# bb-7.net
KiCad netlist of a schematic drawn in EAGLE
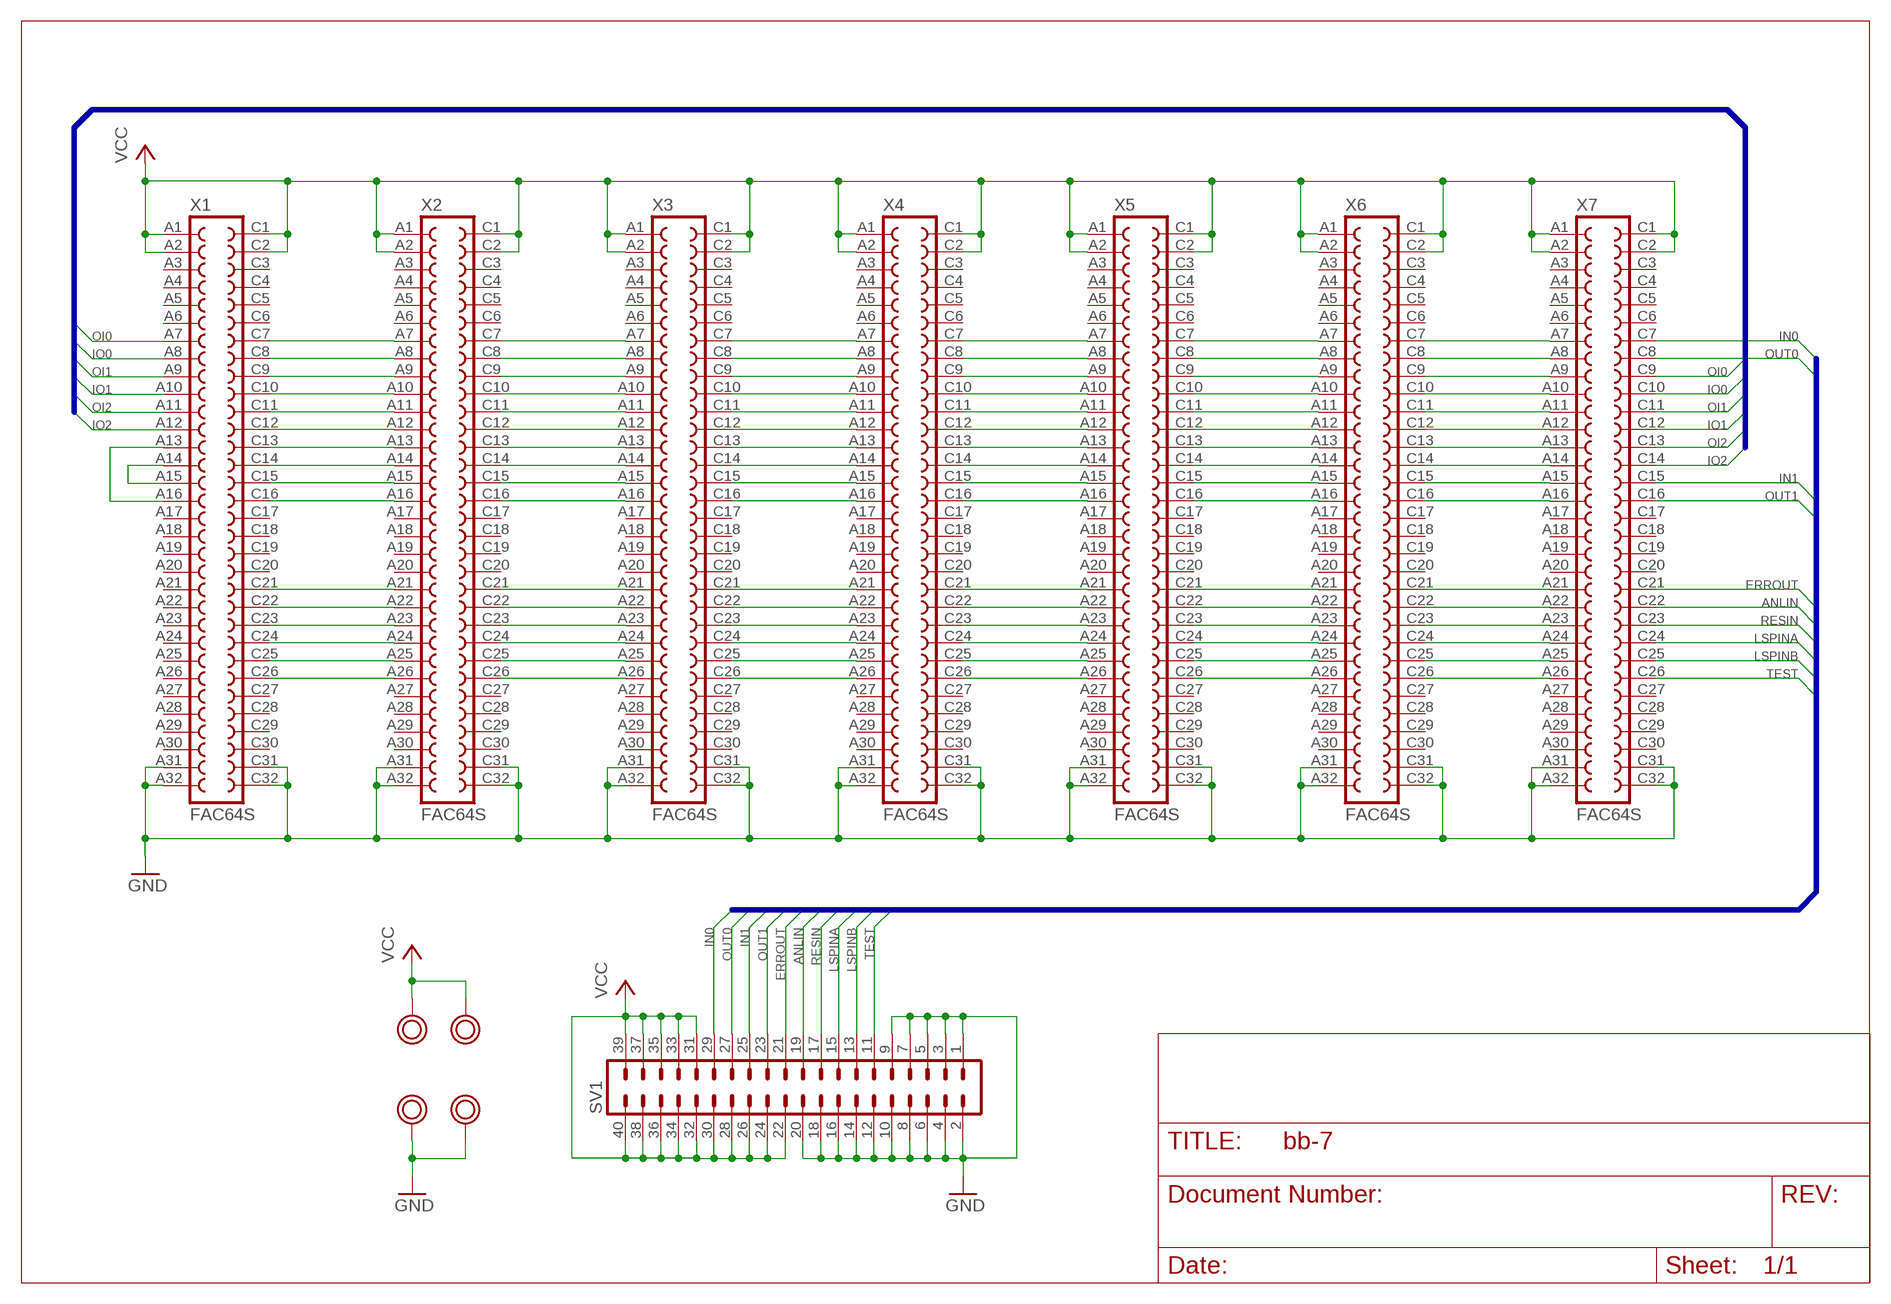
[diagram p0: schematic, sheet 1]

(export (version "E")
  (design (tool "Eeschema 10.0.6"))
  (components
    (comp (ref "SV1")
      (value "MA20-2")
      (footprint "eagle-import:MA20-2")
      (libsource (lib "eagle-import") (part "MA20-2"))
    )
    (comp (ref "U$3")
      (value "POWERPAD")
      (footprint "eagle-import:POWERPAD")
      (libsource (lib "eagle-import") (part "POWERPAD"))
    )
    (comp (ref "U$4")
      (value "POWERPAD")
      (footprint "eagle-import:POWERPAD")
      (libsource (lib "eagle-import") (part "POWERPAD"))
    )
    (comp (ref "U$5")
      (value "POWERPAD")
      (footprint "eagle-import:POWERPAD")
      (libsource (lib "eagle-import") (part "POWERPAD"))
    )
    (comp (ref "U$6")
      (value "POWERPAD")
      (footprint "eagle-import:POWERPAD")
      (libsource (lib "eagle-import") (part "POWERPAD"))
    )
    (comp (ref "X1")
      (value "FAC64S")
      (footprint "eagle-import:FAC64S")
      (libsource (lib "eagle-import") (part "FAC64S"))
    )
    (comp (ref "X2")
      (value "FAC64S")
      (footprint "eagle-import:FAC64S")
      (libsource (lib "eagle-import") (part "FAC64S"))
    )
    (comp (ref "X3")
      (value "FAC64S")
      (footprint "eagle-import:FAC64S")
      (libsource (lib "eagle-import") (part "FAC64S"))
    )
    (comp (ref "X4")
      (value "FAC64S")
      (footprint "eagle-import:FAC64S")
      (libsource (lib "eagle-import") (part "FAC64S"))
    )
    (comp (ref "X5")
      (value "FAC64S")
      (footprint "eagle-import:FAC64S")
      (libsource (lib "eagle-import") (part "FAC64S"))
    )
    (comp (ref "X6")
      (value "FAC64S")
      (footprint "eagle-import:FAC64S")
      (libsource (lib "eagle-import") (part "FAC64S"))
    )
    (comp (ref "X7")
      (value "FAC64S")
      (footprint "eagle-import:FAC64S")
      (libsource (lib "eagle-import") (part "FAC64S"))
    )
  )
  (nets
    (net (code "1") (name "/ANLIN") (class "Default")
      (node (ref "SV1") (pin "19") (pinfunction "19_19") (pintype "passive"))
      (node (ref "X7") (pin "C22") (pinfunction "C22_C22") (pintype "passive"))
    )
    (net (code "2") (name "/ERROUT") (class "Default")
      (node (ref "SV1") (pin "21") (pinfunction "21_21") (pintype "passive"))
      (node (ref "X7") (pin "C21") (pinfunction "C21_C21") (pintype "passive"))
    )
    (net (code "3") (name "/IN0") (class "Default")
      (node (ref "SV1") (pin "29") (pinfunction "29_29") (pintype "passive"))
      (node (ref "X7") (pin "C7") (pinfunction "C7_C7") (pintype "passive"))
    )
    (net (code "4") (name "/IN1") (class "Default")
      (node (ref "SV1") (pin "25") (pinfunction "25_25") (pintype "passive"))
      (node (ref "X7") (pin "C15") (pinfunction "C15_C15") (pintype "passive"))
    )
    (net (code "5") (name "/IO0") (class "Default")
      (node (ref "X1") (pin "A8") (pinfunction "A8_A8") (pintype "passive"))
      (node (ref "X7") (pin "C10") (pinfunction "C10_C10") (pintype "passive"))
    )
    (net (code "6") (name "/IO1") (class "Default")
      (node (ref "X1") (pin "A10") (pinfunction "A10_A10") (pintype "passive"))
      (node (ref "X7") (pin "C12") (pinfunction "C12_C12") (pintype "passive"))
    )
    (net (code "7") (name "/IO2") (class "Default")
      (node (ref "X1") (pin "A12") (pinfunction "A12_A12") (pintype "passive"))
      (node (ref "X7") (pin "C14") (pinfunction "C14_C14") (pintype "passive"))
    )
    (net (code "8") (name "/LSPINA") (class "Default")
      (node (ref "SV1") (pin "15") (pinfunction "15_15") (pintype "passive"))
      (node (ref "X7") (pin "C24") (pinfunction "C24_C24") (pintype "passive"))
    )
    (net (code "9") (name "/LSPINB") (class "Default")
      (node (ref "SV1") (pin "13") (pinfunction "13_13") (pintype "passive"))
      (node (ref "X7") (pin "C25") (pinfunction "C25_C25") (pintype "passive"))
    )
    (net (code "10") (name "/OI0") (class "Default")
      (node (ref "X1") (pin "A7") (pinfunction "A7_A7") (pintype "passive"))
      (node (ref "X7") (pin "C9") (pinfunction "C9_C9") (pintype "passive"))
    )
    (net (code "11") (name "/OI1") (class "Default")
      (node (ref "X1") (pin "A9") (pinfunction "A9_A9") (pintype "passive"))
      (node (ref "X7") (pin "C11") (pinfunction "C11_C11") (pintype "passive"))
    )
    (net (code "12") (name "/OI2") (class "Default")
      (node (ref "X1") (pin "A11") (pinfunction "A11_A11") (pintype "passive"))
      (node (ref "X7") (pin "C13") (pinfunction "C13_C13") (pintype "passive"))
    )
    (net (code "13") (name "/OUT0") (class "Default")
      (node (ref "SV1") (pin "27") (pinfunction "27_27") (pintype "passive"))
      (node (ref "X7") (pin "C8") (pinfunction "C8_C8") (pintype "passive"))
    )
    (net (code "14") (name "/OUT1") (class "Default")
      (node (ref "SV1") (pin "23") (pinfunction "23_23") (pintype "passive"))
      (node (ref "X7") (pin "C16") (pinfunction "C16_C16") (pintype "passive"))
    )
    (net (code "15") (name "/RESIN") (class "Default")
      (node (ref "SV1") (pin "17") (pinfunction "17_17") (pintype "passive"))
      (node (ref "X7") (pin "C23") (pinfunction "C23_C23") (pintype "passive"))
    )
    (net (code "16") (name "/TEST") (class "Default")
      (node (ref "SV1") (pin "11") (pinfunction "11_11") (pintype "passive"))
      (node (ref "X7") (pin "C26") (pinfunction "C26_C26") (pintype "passive"))
    )
    (net (code "17") (name "GND") (class "Default")
      (node (ref "SV1") (pin "1") (pinfunction "1_1") (pintype "passive"))
      (node (ref "SV1") (pin "10") (pinfunction "10_10") (pintype "passive"))
      (node (ref "SV1") (pin "12") (pinfunction "12_12") (pintype "passive"))
      (node (ref "SV1") (pin "14") (pinfunction "14_14") (pintype "passive"))
      (node (ref "SV1") (pin "16") (pinfunction "16_16") (pintype "passive"))
      (node (ref "SV1") (pin "18") (pinfunction "18_18") (pintype "passive"))
      (node (ref "SV1") (pin "2") (pinfunction "2_2") (pintype "passive"))
      (node (ref "SV1") (pin "20") (pinfunction "20_20") (pintype "passive"))
      (node (ref "SV1") (pin "3") (pinfunction "3_3") (pintype "passive"))
      (node (ref "SV1") (pin "4") (pinfunction "4_4") (pintype "passive"))
      (node (ref "SV1") (pin "5") (pinfunction "5_5") (pintype "passive"))
      (node (ref "SV1") (pin "6") (pinfunction "6_6") (pintype "passive"))
      (node (ref "SV1") (pin "7") (pinfunction "7_7") (pintype "passive"))
      (node (ref "SV1") (pin "8") (pinfunction "8_8") (pintype "passive"))
      (node (ref "SV1") (pin "9") (pinfunction "9_9") (pintype "passive"))
      (node (ref "U$3") (pin "P$1") (pinfunction "P$1_P$1") (pintype "bidirectional"))
      (node (ref "U$4") (pin "P$1") (pinfunction "P$1_P$1") (pintype "bidirectional"))
      (node (ref "X1") (pin "A31") (pinfunction "A31_A31") (pintype "passive"))
      (node (ref "X1") (pin "A32") (pinfunction "A32_A32") (pintype "passive"))
      (node (ref "X1") (pin "C31") (pinfunction "C31_C31") (pintype "passive"))
      (node (ref "X1") (pin "C32") (pinfunction "C32_C32") (pintype "passive"))
      (node (ref "X2") (pin "A31") (pinfunction "A31_A31") (pintype "passive"))
      (node (ref "X2") (pin "A32") (pinfunction "A32_A32") (pintype "passive"))
      (node (ref "X2") (pin "C31") (pinfunction "C31_C31") (pintype "passive"))
      (node (ref "X2") (pin "C32") (pinfunction "C32_C32") (pintype "passive"))
      (node (ref "X3") (pin "A31") (pinfunction "A31_A31") (pintype "passive"))
      (node (ref "X3") (pin "A32") (pinfunction "A32_A32") (pintype "passive"))
      (node (ref "X3") (pin "C31") (pinfunction "C31_C31") (pintype "passive"))
      (node (ref "X3") (pin "C32") (pinfunction "C32_C32") (pintype "passive"))
      (node (ref "X4") (pin "A31") (pinfunction "A31_A31") (pintype "passive"))
      (node (ref "X4") (pin "A32") (pinfunction "A32_A32") (pintype "passive"))
      (node (ref "X4") (pin "C31") (pinfunction "C31_C31") (pintype "passive"))
      (node (ref "X4") (pin "C32") (pinfunction "C32_C32") (pintype "passive"))
      (node (ref "X5") (pin "A31") (pinfunction "A31_A31") (pintype "passive"))
      (node (ref "X5") (pin "A32") (pinfunction "A32_A32") (pintype "passive"))
      (node (ref "X5") (pin "C31") (pinfunction "C31_C31") (pintype "passive"))
      (node (ref "X5") (pin "C32") (pinfunction "C32_C32") (pintype "passive"))
      (node (ref "X6") (pin "A31") (pinfunction "A31_A31") (pintype "passive"))
      (node (ref "X6") (pin "A32") (pinfunction "A32_A32") (pintype "passive"))
      (node (ref "X6") (pin "C31") (pinfunction "C31_C31") (pintype "passive"))
      (node (ref "X6") (pin "C32") (pinfunction "C32_C32") (pintype "passive"))
      (node (ref "X7") (pin "A31") (pinfunction "A31_A31") (pintype "passive"))
      (node (ref "X7") (pin "A32") (pinfunction "A32_A32") (pintype "passive"))
      (node (ref "X7") (pin "C31") (pinfunction "C31_C31") (pintype "passive"))
      (node (ref "X7") (pin "C32") (pinfunction "C32_C32") (pintype "passive"))
    )
    (net (code "18") (name "Net-(X1-PadA13)") (class "Default")
      (node (ref "X1") (pin "A13") (pinfunction "A13_A13") (pintype "passive"))
      (node (ref "X1") (pin "A16") (pinfunction "A16_A16") (pintype "passive"))
    )
    (net (code "19") (name "Net-(X1-PadA14)") (class "Default")
      (node (ref "X1") (pin "A14") (pinfunction "A14_A14") (pintype "passive"))
      (node (ref "X1") (pin "A15") (pinfunction "A15_A15") (pintype "passive"))
    )
    (net (code "20") (name "Net-(X1-PadC7)") (class "Default")
      (node (ref "X1") (pin "C7") (pinfunction "C7_C7") (pintype "passive"))
      (node (ref "X2") (pin "A7") (pinfunction "A7_A7") (pintype "passive"))
    )
    (net (code "21") (name "Net-(X1-PadC8)") (class "Default")
      (node (ref "X1") (pin "C8") (pinfunction "C8_C8") (pintype "passive"))
      (node (ref "X2") (pin "A8") (pinfunction "A8_A8") (pintype "passive"))
    )
    (net (code "22") (name "Net-(X1-PadC9)") (class "Default")
      (node (ref "X1") (pin "C9") (pinfunction "C9_C9") (pintype "passive"))
      (node (ref "X2") (pin "A9") (pinfunction "A9_A9") (pintype "passive"))
    )
    (net (code "23") (name "Net-(X1-PadC10)") (class "Default")
      (node (ref "X1") (pin "C10") (pinfunction "C10_C10") (pintype "passive"))
      (node (ref "X2") (pin "A10") (pinfunction "A10_A10") (pintype "passive"))
    )
    (net (code "24") (name "Net-(X1-PadC11)") (class "Default")
      (node (ref "X1") (pin "C11") (pinfunction "C11_C11") (pintype "passive"))
      (node (ref "X2") (pin "A11") (pinfunction "A11_A11") (pintype "passive"))
    )
    (net (code "25") (name "Net-(X1-PadC12)") (class "Default")
      (node (ref "X1") (pin "C12") (pinfunction "C12_C12") (pintype "passive"))
      (node (ref "X2") (pin "A12") (pinfunction "A12_A12") (pintype "passive"))
    )
    (net (code "26") (name "Net-(X1-PadC13)") (class "Default")
      (node (ref "X1") (pin "C13") (pinfunction "C13_C13") (pintype "passive"))
      (node (ref "X2") (pin "A13") (pinfunction "A13_A13") (pintype "passive"))
    )
    (net (code "27") (name "Net-(X1-PadC14)") (class "Default")
      (node (ref "X1") (pin "C14") (pinfunction "C14_C14") (pintype "passive"))
      (node (ref "X2") (pin "A14") (pinfunction "A14_A14") (pintype "passive"))
    )
    (net (code "28") (name "Net-(X1-PadC15)") (class "Default")
      (node (ref "X1") (pin "C15") (pinfunction "C15_C15") (pintype "passive"))
      (node (ref "X2") (pin "A15") (pinfunction "A15_A15") (pintype "passive"))
    )
    (net (code "29") (name "Net-(X1-PadC16)") (class "Default")
      (node (ref "X1") (pin "C16") (pinfunction "C16_C16") (pintype "passive"))
      (node (ref "X2") (pin "A16") (pinfunction "A16_A16") (pintype "passive"))
    )
    (net (code "30") (name "Net-(X1-PadC21)") (class "Default")
      (node (ref "X1") (pin "C21") (pinfunction "C21_C21") (pintype "passive"))
      (node (ref "X2") (pin "A21") (pinfunction "A21_A21") (pintype "passive"))
    )
    (net (code "31") (name "Net-(X1-PadC22)") (class "Default")
      (node (ref "X1") (pin "C22") (pinfunction "C22_C22") (pintype "passive"))
      (node (ref "X2") (pin "A22") (pinfunction "A22_A22") (pintype "passive"))
    )
    (net (code "32") (name "Net-(X1-PadC23)") (class "Default")
      (node (ref "X1") (pin "C23") (pinfunction "C23_C23") (pintype "passive"))
      (node (ref "X2") (pin "A23") (pinfunction "A23_A23") (pintype "passive"))
    )
    (net (code "33") (name "Net-(X1-PadC24)") (class "Default")
      (node (ref "X1") (pin "C24") (pinfunction "C24_C24") (pintype "passive"))
      (node (ref "X2") (pin "A24") (pinfunction "A24_A24") (pintype "passive"))
    )
    (net (code "34") (name "Net-(X1-PadC25)") (class "Default")
      (node (ref "X1") (pin "C25") (pinfunction "C25_C25") (pintype "passive"))
      (node (ref "X2") (pin "A25") (pinfunction "A25_A25") (pintype "passive"))
    )
    (net (code "35") (name "Net-(X1-PadC26)") (class "Default")
      (node (ref "X1") (pin "C26") (pinfunction "C26_C26") (pintype "passive"))
      (node (ref "X2") (pin "A26") (pinfunction "A26_A26") (pintype "passive"))
    )
    (net (code "36") (name "Net-(X2-PadC7)") (class "Default")
      (node (ref "X2") (pin "C7") (pinfunction "C7_C7") (pintype "passive"))
      (node (ref "X3") (pin "A7") (pinfunction "A7_A7") (pintype "passive"))
    )
    (net (code "37") (name "Net-(X2-PadC8)") (class "Default")
      (node (ref "X2") (pin "C8") (pinfunction "C8_C8") (pintype "passive"))
      (node (ref "X3") (pin "A8") (pinfunction "A8_A8") (pintype "passive"))
    )
    (net (code "38") (name "Net-(X2-PadC9)") (class "Default")
      (node (ref "X2") (pin "C9") (pinfunction "C9_C9") (pintype "passive"))
      (node (ref "X3") (pin "A9") (pinfunction "A9_A9") (pintype "passive"))
    )
    (net (code "39") (name "Net-(X2-PadC10)") (class "Default")
      (node (ref "X2") (pin "C10") (pinfunction "C10_C10") (pintype "passive"))
      (node (ref "X3") (pin "A10") (pinfunction "A10_A10") (pintype "passive"))
    )
    (net (code "40") (name "Net-(X2-PadC11)") (class "Default")
      (node (ref "X2") (pin "C11") (pinfunction "C11_C11") (pintype "passive"))
      (node (ref "X3") (pin "A11") (pinfunction "A11_A11") (pintype "passive"))
    )
    (net (code "41") (name "Net-(X2-PadC12)") (class "Default")
      (node (ref "X2") (pin "C12") (pinfunction "C12_C12") (pintype "passive"))
      (node (ref "X3") (pin "A12") (pinfunction "A12_A12") (pintype "passive"))
    )
    (net (code "42") (name "Net-(X2-PadC13)") (class "Default")
      (node (ref "X2") (pin "C13") (pinfunction "C13_C13") (pintype "passive"))
      (node (ref "X3") (pin "A13") (pinfunction "A13_A13") (pintype "passive"))
    )
    (net (code "43") (name "Net-(X2-PadC14)") (class "Default")
      (node (ref "X2") (pin "C14") (pinfunction "C14_C14") (pintype "passive"))
      (node (ref "X3") (pin "A14") (pinfunction "A14_A14") (pintype "passive"))
    )
    (net (code "44") (name "Net-(X2-PadC15)") (class "Default")
      (node (ref "X2") (pin "C15") (pinfunction "C15_C15") (pintype "passive"))
      (node (ref "X3") (pin "A15") (pinfunction "A15_A15") (pintype "passive"))
    )
    (net (code "45") (name "Net-(X2-PadC16)") (class "Default")
      (node (ref "X2") (pin "C16") (pinfunction "C16_C16") (pintype "passive"))
      (node (ref "X3") (pin "A16") (pinfunction "A16_A16") (pintype "passive"))
    )
    (net (code "46") (name "Net-(X2-PadC21)") (class "Default")
      (node (ref "X2") (pin "C21") (pinfunction "C21_C21") (pintype "passive"))
      (node (ref "X3") (pin "A21") (pinfunction "A21_A21") (pintype "passive"))
    )
    (net (code "47") (name "Net-(X2-PadC22)") (class "Default")
      (node (ref "X2") (pin "C22") (pinfunction "C22_C22") (pintype "passive"))
      (node (ref "X3") (pin "A22") (pinfunction "A22_A22") (pintype "passive"))
    )
    (net (code "48") (name "Net-(X2-PadC23)") (class "Default")
      (node (ref "X2") (pin "C23") (pinfunction "C23_C23") (pintype "passive"))
      (node (ref "X3") (pin "A23") (pinfunction "A23_A23") (pintype "passive"))
    )
    (net (code "49") (name "Net-(X2-PadC24)") (class "Default")
      (node (ref "X2") (pin "C24") (pinfunction "C24_C24") (pintype "passive"))
      (node (ref "X3") (pin "A24") (pinfunction "A24_A24") (pintype "passive"))
    )
    (net (code "50") (name "Net-(X2-PadC25)") (class "Default")
      (node (ref "X2") (pin "C25") (pinfunction "C25_C25") (pintype "passive"))
      (node (ref "X3") (pin "A25") (pinfunction "A25_A25") (pintype "passive"))
    )
    (net (code "51") (name "Net-(X2-PadC26)") (class "Default")
      (node (ref "X2") (pin "C26") (pinfunction "C26_C26") (pintype "passive"))
      (node (ref "X3") (pin "A26") (pinfunction "A26_A26") (pintype "passive"))
    )
    (net (code "52") (name "Net-(X3-PadC7)") (class "Default")
      (node (ref "X3") (pin "C7") (pinfunction "C7_C7") (pintype "passive"))
      (node (ref "X4") (pin "A7") (pinfunction "A7_A7") (pintype "passive"))
    )
    (net (code "53") (name "Net-(X3-PadC8)") (class "Default")
      (node (ref "X3") (pin "C8") (pinfunction "C8_C8") (pintype "passive"))
      (node (ref "X4") (pin "A8") (pinfunction "A8_A8") (pintype "passive"))
    )
    (net (code "54") (name "Net-(X3-PadC9)") (class "Default")
      (node (ref "X3") (pin "C9") (pinfunction "C9_C9") (pintype "passive"))
      (node (ref "X4") (pin "A9") (pinfunction "A9_A9") (pintype "passive"))
    )
    (net (code "55") (name "Net-(X3-PadC10)") (class "Default")
      (node (ref "X3") (pin "C10") (pinfunction "C10_C10") (pintype "passive"))
      (node (ref "X4") (pin "A10") (pinfunction "A10_A10") (pintype "passive"))
    )
    (net (code "56") (name "Net-(X3-PadC11)") (class "Default")
      (node (ref "X3") (pin "C11") (pinfunction "C11_C11") (pintype "passive"))
      (node (ref "X4") (pin "A11") (pinfunction "A11_A11") (pintype "passive"))
    )
    (net (code "57") (name "Net-(X3-PadC12)") (class "Default")
      (node (ref "X3") (pin "C12") (pinfunction "C12_C12") (pintype "passive"))
      (node (ref "X4") (pin "A12") (pinfunction "A12_A12") (pintype "passive"))
    )
    (net (code "58") (name "Net-(X3-PadC13)") (class "Default")
      (node (ref "X3") (pin "C13") (pinfunction "C13_C13") (pintype "passive"))
      (node (ref "X4") (pin "A13") (pinfunction "A13_A13") (pintype "passive"))
    )
    (net (code "59") (name "Net-(X3-PadC14)") (class "Default")
      (node (ref "X3") (pin "C14") (pinfunction "C14_C14") (pintype "passive"))
      (node (ref "X4") (pin "A14") (pinfunction "A14_A14") (pintype "passive"))
    )
    (net (code "60") (name "Net-(X3-PadC15)") (class "Default")
      (node (ref "X3") (pin "C15") (pinfunction "C15_C15") (pintype "passive"))
      (node (ref "X4") (pin "A15") (pinfunction "A15_A15") (pintype "passive"))
    )
    (net (code "61") (name "Net-(X3-PadC16)") (class "Default")
      (node (ref "X3") (pin "C16") (pinfunction "C16_C16") (pintype "passive"))
      (node (ref "X4") (pin "A16") (pinfunction "A16_A16") (pintype "passive"))
    )
    (net (code "62") (name "Net-(X3-PadC21)") (class "Default")
      (node (ref "X3") (pin "C21") (pinfunction "C21_C21") (pintype "passive"))
      (node (ref "X4") (pin "A21") (pinfunction "A21_A21") (pintype "passive"))
    )
    (net (code "63") (name "Net-(X3-PadC22)") (class "Default")
      (node (ref "X3") (pin "C22") (pinfunction "C22_C22") (pintype "passive"))
      (node (ref "X4") (pin "A22") (pinfunction "A22_A22") (pintype "passive"))
    )
    (net (code "64") (name "Net-(X3-PadC23)") (class "Default")
      (node (ref "X3") (pin "C23") (pinfunction "C23_C23") (pintype "passive"))
      (node (ref "X4") (pin "A23") (pinfunction "A23_A23") (pintype "passive"))
    )
    (net (code "65") (name "Net-(X3-PadC24)") (class "Default")
      (node (ref "X3") (pin "C24") (pinfunction "C24_C24") (pintype "passive"))
      (node (ref "X4") (pin "A24") (pinfunction "A24_A24") (pintype "passive"))
    )
    (net (code "66") (name "Net-(X3-PadC25)") (class "Default")
      (node (ref "X3") (pin "C25") (pinfunction "C25_C25") (pintype "passive"))
      (node (ref "X4") (pin "A25") (pinfunction "A25_A25") (pintype "passive"))
    )
    (net (code "67") (name "Net-(X3-PadC26)") (class "Default")
      (node (ref "X3") (pin "C26") (pinfunction "C26_C26") (pintype "passive"))
      (node (ref "X4") (pin "A26") (pinfunction "A26_A26") (pintype "passive"))
    )
    (net (code "68") (name "Net-(X4-PadC7)") (class "Default")
      (node (ref "X4") (pin "C7") (pinfunction "C7_C7") (pintype "passive"))
      (node (ref "X5") (pin "A7") (pinfunction "A7_A7") (pintype "passive"))
    )
    (net (code "69") (name "Net-(X4-PadC8)") (class "Default")
      (node (ref "X4") (pin "C8") (pinfunction "C8_C8") (pintype "passive"))
      (node (ref "X5") (pin "A8") (pinfunction "A8_A8") (pintype "passive"))
    )
    (net (code "70") (name "Net-(X4-PadC9)") (class "Default")
      (node (ref "X4") (pin "C9") (pinfunction "C9_C9") (pintype "passive"))
      (node (ref "X5") (pin "A9") (pinfunction "A9_A9") (pintype "passive"))
    )
    (net (code "71") (name "Net-(X4-PadC10)") (class "Default")
      (node (ref "X4") (pin "C10") (pinfunction "C10_C10") (pintype "passive"))
      (node (ref "X5") (pin "A10") (pinfunction "A10_A10") (pintype "passive"))
    )
    (net (code "72") (name "Net-(X4-PadC11)") (class "Default")
      (node (ref "X4") (pin "C11") (pinfunction "C11_C11") (pintype "passive"))
      (node (ref "X5") (pin "A11") (pinfunction "A11_A11") (pintype "passive"))
    )
    (net (code "73") (name "Net-(X4-PadC12)") (class "Default")
      (node (ref "X4") (pin "C12") (pinfunction "C12_C12") (pintype "passive"))
      (node (ref "X5") (pin "A12") (pinfunction "A12_A12") (pintype "passive"))
    )
    (net (code "74") (name "Net-(X4-PadC13)") (class "Default")
      (node (ref "X4") (pin "C13") (pinfunction "C13_C13") (pintype "passive"))
      (node (ref "X5") (pin "A13") (pinfunction "A13_A13") (pintype "passive"))
    )
    (net (code "75") (name "Net-(X4-PadC14)") (class "Default")
      (node (ref "X4") (pin "C14") (pinfunction "C14_C14") (pintype "passive"))
      (node (ref "X5") (pin "A14") (pinfunction "A14_A14") (pintype "passive"))
    )
    (net (code "76") (name "Net-(X4-PadC15)") (class "Default")
      (node (ref "X4") (pin "C15") (pinfunction "C15_C15") (pintype "passive"))
      (node (ref "X5") (pin "A15") (pinfunction "A15_A15") (pintype "passive"))
    )
    (net (code "77") (name "Net-(X4-PadC16)") (class "Default")
      (node (ref "X4") (pin "C16") (pinfunction "C16_C16") (pintype "passive"))
      (node (ref "X5") (pin "A16") (pinfunction "A16_A16") (pintype "passive"))
    )
    (net (code "78") (name "Net-(X4-PadC21)") (class "Default")
      (node (ref "X4") (pin "C21") (pinfunction "C21_C21") (pintype "passive"))
      (node (ref "X5") (pin "A21") (pinfunction "A21_A21") (pintype "passive"))
    )
    (net (code "79") (name "Net-(X4-PadC22)") (class "Default")
      (node (ref "X4") (pin "C22") (pinfunction "C22_C22") (pintype "passive"))
      (node (ref "X5") (pin "A22") (pinfunction "A22_A22") (pintype "passive"))
    )
    (net (code "80") (name "Net-(X4-PadC23)") (class "Default")
      (node (ref "X4") (pin "C23") (pinfunction "C23_C23") (pintype "passive"))
      (node (ref "X5") (pin "A23") (pinfunction "A23_A23") (pintype "passive"))
    )
    (net (code "81") (name "Net-(X4-PadC24)") (class "Default")
      (node (ref "X4") (pin "C24") (pinfunction "C24_C24") (pintype "passive"))
      (node (ref "X5") (pin "A24") (pinfunction "A24_A24") (pintype "passive"))
    )
    (net (code "82") (name "Net-(X4-PadC25)") (class "Default")
      (node (ref "X4") (pin "C25") (pinfunction "C25_C25") (pintype "passive"))
      (node (ref "X5") (pin "A25") (pinfunction "A25_A25") (pintype "passive"))
    )
    (net (code "83") (name "Net-(X4-PadC26)") (class "Default")
      (node (ref "X4") (pin "C26") (pinfunction "C26_C26") (pintype "passive"))
      (node (ref "X5") (pin "A26") (pinfunction "A26_A26") (pintype "passive"))
    )
    (net (code "84") (name "Net-(X5-PadC7)") (class "Default")
      (node (ref "X5") (pin "C7") (pinfunction "C7_C7") (pintype "passive"))
      (node (ref "X6") (pin "A7") (pinfunction "A7_A7") (pintype "passive"))
    )
    (net (code "85") (name "Net-(X5-PadC8)") (class "Default")
      (node (ref "X5") (pin "C8") (pinfunction "C8_C8") (pintype "passive"))
      (node (ref "X6") (pin "A8") (pinfunction "A8_A8") (pintype "passive"))
    )
    (net (code "86") (name "Net-(X5-PadC9)") (class "Default")
      (node (ref "X5") (pin "C9") (pinfunction "C9_C9") (pintype "passive"))
      (node (ref "X6") (pin "A9") (pinfunction "A9_A9") (pintype "passive"))
    )
    (net (code "87") (name "Net-(X5-PadC10)") (class "Default")
      (node (ref "X5") (pin "C10") (pinfunction "C10_C10") (pintype "passive"))
      (node (ref "X6") (pin "A10") (pinfunction "A10_A10") (pintype "passive"))
    )
    (net (code "88") (name "Net-(X5-PadC11)") (class "Default")
      (node (ref "X5") (pin "C11") (pinfunction "C11_C11") (pintype "passive"))
      (node (ref "X6") (pin "A11") (pinfunction "A11_A11") (pintype "passive"))
    )
    (net (code "89") (name "Net-(X5-PadC12)") (class "Default")
      (node (ref "X5") (pin "C12") (pinfunction "C12_C12") (pintype "passive"))
      (node (ref "X6") (pin "A12") (pinfunction "A12_A12") (pintype "passive"))
    )
    (net (code "90") (name "Net-(X5-PadC13)") (class "Default")
      (node (ref "X5") (pin "C13") (pinfunction "C13_C13") (pintype "passive"))
      (node (ref "X6") (pin "A13") (pinfunction "A13_A13") (pintype "passive"))
    )
    (net (code "91") (name "Net-(X5-PadC14)") (class "Default")
      (node (ref "X5") (pin "C14") (pinfunction "C14_C14") (pintype "passive"))
      (node (ref "X6") (pin "A14") (pinfunction "A14_A14") (pintype "passive"))
    )
    (net (code "92") (name "Net-(X5-PadC15)") (class "Default")
      (node (ref "X5") (pin "C15") (pinfunction "C15_C15") (pintype "passive"))
      (node (ref "X6") (pin "A15") (pinfunction "A15_A15") (pintype "passive"))
    )
    (net (code "93") (name "Net-(X5-PadC16)") (class "Default")
      (node (ref "X5") (pin "C16") (pinfunction "C16_C16") (pintype "passive"))
      (node (ref "X6") (pin "A16") (pinfunction "A16_A16") (pintype "passive"))
    )
    (net (code "94") (name "Net-(X5-PadC21)") (class "Default")
      (node (ref "X5") (pin "C21") (pinfunction "C21_C21") (pintype "passive"))
      (node (ref "X6") (pin "A21") (pinfunction "A21_A21") (pintype "passive"))
    )
    (net (code "95") (name "Net-(X5-PadC22)") (class "Default")
      (node (ref "X5") (pin "C22") (pinfunction "C22_C22") (pintype "passive"))
      (node (ref "X6") (pin "A22") (pinfunction "A22_A22") (pintype "passive"))
    )
    (net (code "96") (name "Net-(X5-PadC23)") (class "Default")
      (node (ref "X5") (pin "C23") (pinfunction "C23_C23") (pintype "passive"))
      (node (ref "X6") (pin "A23") (pinfunction "A23_A23") (pintype "passive"))
    )
    (net (code "97") (name "Net-(X5-PadC24)") (class "Default")
      (node (ref "X5") (pin "C24") (pinfunction "C24_C24") (pintype "passive"))
      (node (ref "X6") (pin "A24") (pinfunction "A24_A24") (pintype "passive"))
    )
    (net (code "98") (name "Net-(X5-PadC25)") (class "Default")
      (node (ref "X5") (pin "C25") (pinfunction "C25_C25") (pintype "passive"))
      (node (ref "X6") (pin "A25") (pinfunction "A25_A25") (pintype "passive"))
    )
    (net (code "99") (name "Net-(X5-PadC26)") (class "Default")
      (node (ref "X5") (pin "C26") (pinfunction "C26_C26") (pintype "passive"))
      (node (ref "X6") (pin "A26") (pinfunction "A26_A26") (pintype "passive"))
    )
    (net (code "100") (name "Net-(X6-PadC7)") (class "Default")
      (node (ref "X6") (pin "C7") (pinfunction "C7_C7") (pintype "passive"))
      (node (ref "X7") (pin "A7") (pinfunction "A7_A7") (pintype "passive"))
    )
    (net (code "101") (name "Net-(X6-PadC8)") (class "Default")
      (node (ref "X6") (pin "C8") (pinfunction "C8_C8") (pintype "passive"))
      (node (ref "X7") (pin "A8") (pinfunction "A8_A8") (pintype "passive"))
    )
    (net (code "102") (name "Net-(X6-PadC9)") (class "Default")
      (node (ref "X6") (pin "C9") (pinfunction "C9_C9") (pintype "passive"))
      (node (ref "X7") (pin "A9") (pinfunction "A9_A9") (pintype "passive"))
    )
    (net (code "103") (name "Net-(X6-PadC10)") (class "Default")
      (node (ref "X6") (pin "C10") (pinfunction "C10_C10") (pintype "passive"))
      (node (ref "X7") (pin "A10") (pinfunction "A10_A10") (pintype "passive"))
    )
    (net (code "104") (name "Net-(X6-PadC11)") (class "Default")
      (node (ref "X6") (pin "C11") (pinfunction "C11_C11") (pintype "passive"))
      (node (ref "X7") (pin "A11") (pinfunction "A11_A11") (pintype "passive"))
    )
    (net (code "105") (name "Net-(X6-PadC12)") (class "Default")
      (node (ref "X6") (pin "C12") (pinfunction "C12_C12") (pintype "passive"))
      (node (ref "X7") (pin "A12") (pinfunction "A12_A12") (pintype "passive"))
    )
    (net (code "106") (name "Net-(X6-PadC13)") (class "Default")
      (node (ref "X6") (pin "C13") (pinfunction "C13_C13") (pintype "passive"))
      (node (ref "X7") (pin "A13") (pinfunction "A13_A13") (pintype "passive"))
    )
    (net (code "107") (name "Net-(X6-PadC14)") (class "Default")
      (node (ref "X6") (pin "C14") (pinfunction "C14_C14") (pintype "passive"))
      (node (ref "X7") (pin "A14") (pinfunction "A14_A14") (pintype "passive"))
    )
    (net (code "108") (name "Net-(X6-PadC15)") (class "Default")
      (node (ref "X6") (pin "C15") (pinfunction "C15_C15") (pintype "passive"))
      (node (ref "X7") (pin "A15") (pinfunction "A15_A15") (pintype "passive"))
    )
    (net (code "109") (name "Net-(X6-PadC16)") (class "Default")
      (node (ref "X6") (pin "C16") (pinfunction "C16_C16") (pintype "passive"))
      (node (ref "X7") (pin "A16") (pinfunction "A16_A16") (pintype "passive"))
    )
    (net (code "110") (name "Net-(X6-PadC21)") (class "Default")
      (node (ref "X6") (pin "C21") (pinfunction "C21_C21") (pintype "passive"))
      (node (ref "X7") (pin "A21") (pinfunction "A21_A21") (pintype "passive"))
    )
    (net (code "111") (name "Net-(X6-PadC22)") (class "Default")
      (node (ref "X6") (pin "C22") (pinfunction "C22_C22") (pintype "passive"))
      (node (ref "X7") (pin "A22") (pinfunction "A22_A22") (pintype "passive"))
    )
    (net (code "112") (name "Net-(X6-PadC23)") (class "Default")
      (node (ref "X6") (pin "C23") (pinfunction "C23_C23") (pintype "passive"))
      (node (ref "X7") (pin "A23") (pinfunction "A23_A23") (pintype "passive"))
    )
    (net (code "113") (name "Net-(X6-PadC24)") (class "Default")
      (node (ref "X6") (pin "C24") (pinfunction "C24_C24") (pintype "passive"))
      (node (ref "X7") (pin "A24") (pinfunction "A24_A24") (pintype "passive"))
    )
    (net (code "114") (name "Net-(X6-PadC25)") (class "Default")
      (node (ref "X6") (pin "C25") (pinfunction "C25_C25") (pintype "passive"))
      (node (ref "X7") (pin "A25") (pinfunction "A25_A25") (pintype "passive"))
    )
    (net (code "115") (name "Net-(X6-PadC26)") (class "Default")
      (node (ref "X6") (pin "C26") (pinfunction "C26_C26") (pintype "passive"))
      (node (ref "X7") (pin "A26") (pinfunction "A26_A26") (pintype "passive"))
    )
    (net (code "116") (name "VCC") (class "Default")
      (node (ref "SV1") (pin "22") (pinfunction "22_22") (pintype "passive"))
      (node (ref "SV1") (pin "24") (pinfunction "24_24") (pintype "passive"))
      (node (ref "SV1") (pin "26") (pinfunction "26_26") (pintype "passive"))
      (node (ref "SV1") (pin "28") (pinfunction "28_28") (pintype "passive"))
      (node (ref "SV1") (pin "30") (pinfunction "30_30") (pintype "passive"))
      (node (ref "SV1") (pin "31") (pinfunction "31_31") (pintype "passive"))
      (node (ref "SV1") (pin "32") (pinfunction "32_32") (pintype "passive"))
      (node (ref "SV1") (pin "33") (pinfunction "33_33") (pintype "passive"))
      (node (ref "SV1") (pin "34") (pinfunction "34_34") (pintype "passive"))
      (node (ref "SV1") (pin "35") (pinfunction "35_35") (pintype "passive"))
      (node (ref "SV1") (pin "36") (pinfunction "36_36") (pintype "passive"))
      (node (ref "SV1") (pin "37") (pinfunction "37_37") (pintype "passive"))
      (node (ref "SV1") (pin "38") (pinfunction "38_38") (pintype "passive"))
      (node (ref "SV1") (pin "39") (pinfunction "39_39") (pintype "passive"))
      (node (ref "SV1") (pin "40") (pinfunction "40_40") (pintype "passive"))
      (node (ref "U$5") (pin "P$1") (pinfunction "P$1_P$1") (pintype "bidirectional"))
      (node (ref "U$6") (pin "P$1") (pinfunction "P$1_P$1") (pintype "bidirectional"))
      (node (ref "X1") (pin "A1") (pinfunction "A1_A1") (pintype "passive"))
      (node (ref "X1") (pin "A2") (pinfunction "A2_A2") (pintype "passive"))
      (node (ref "X1") (pin "C1") (pinfunction "C1_C1") (pintype "passive"))
      (node (ref "X1") (pin "C2") (pinfunction "C2_C2") (pintype "passive"))
      (node (ref "X2") (pin "A1") (pinfunction "A1_A1") (pintype "passive"))
      (node (ref "X2") (pin "A2") (pinfunction "A2_A2") (pintype "passive"))
      (node (ref "X2") (pin "C1") (pinfunction "C1_C1") (pintype "passive"))
      (node (ref "X2") (pin "C2") (pinfunction "C2_C2") (pintype "passive"))
      (node (ref "X3") (pin "A1") (pinfunction "A1_A1") (pintype "passive"))
      (node (ref "X3") (pin "A2") (pinfunction "A2_A2") (pintype "passive"))
      (node (ref "X3") (pin "C1") (pinfunction "C1_C1") (pintype "passive"))
      (node (ref "X3") (pin "C2") (pinfunction "C2_C2") (pintype "passive"))
      (node (ref "X4") (pin "A1") (pinfunction "A1_A1") (pintype "passive"))
      (node (ref "X4") (pin "A2") (pinfunction "A2_A2") (pintype "passive"))
      (node (ref "X4") (pin "C1") (pinfunction "C1_C1") (pintype "passive"))
      (node (ref "X4") (pin "C2") (pinfunction "C2_C2") (pintype "passive"))
      (node (ref "X5") (pin "A1") (pinfunction "A1_A1") (pintype "passive"))
      (node (ref "X5") (pin "A2") (pinfunction "A2_A2") (pintype "passive"))
      (node (ref "X5") (pin "C1") (pinfunction "C1_C1") (pintype "passive"))
      (node (ref "X5") (pin "C2") (pinfunction "C2_C2") (pintype "passive"))
      (node (ref "X6") (pin "A1") (pinfunction "A1_A1") (pintype "passive"))
      (node (ref "X6") (pin "A2") (pinfunction "A2_A2") (pintype "passive"))
      (node (ref "X6") (pin "C1") (pinfunction "C1_C1") (pintype "passive"))
      (node (ref "X6") (pin "C2") (pinfunction "C2_C2") (pintype "passive"))
      (node (ref "X7") (pin "A1") (pinfunction "A1_A1") (pintype "passive"))
      (node (ref "X7") (pin "A2") (pinfunction "A2_A2") (pintype "passive"))
      (node (ref "X7") (pin "C1") (pinfunction "C1_C1") (pintype "passive"))
      (node (ref "X7") (pin "C2") (pinfunction "C2_C2") (pintype "passive"))
    )
    (net (code "117") (name "unconnected-(X1-PadA3)") (class "Default")
      (node (ref "X1") (pin "A3") (pinfunction "A3_A3") (pintype "passive"))
    )
    (net (code "118") (name "unconnected-(X1-PadA4)") (class "Default")
      (node (ref "X1") (pin "A4") (pinfunction "A4_A4") (pintype "passive"))
    )
    (net (code "119") (name "unconnected-(X1-PadA5)") (class "Default")
      (node (ref "X1") (pin "A5") (pinfunction "A5_A5") (pintype "passive"))
    )
    (net (code "120") (name "unconnected-(X1-PadA6)") (class "Default")
      (node (ref "X1") (pin "A6") (pinfunction "A6_A6") (pintype "passive"))
    )
    (net (code "121") (name "unconnected-(X1-PadA17)") (class "Default")
      (node (ref "X1") (pin "A17") (pinfunction "A17_A17") (pintype "passive"))
    )
    (net (code "122") (name "unconnected-(X1-PadA18)") (class "Default")
      (node (ref "X1") (pin "A18") (pinfunction "A18_A18") (pintype "passive"))
    )
    (net (code "123") (name "unconnected-(X1-PadA19)") (class "Default")
      (node (ref "X1") (pin "A19") (pinfunction "A19_A19") (pintype "passive"))
    )
    (net (code "124") (name "unconnected-(X1-PadA20)") (class "Default")
      (node (ref "X1") (pin "A20") (pinfunction "A20_A20") (pintype "passive"))
    )
    (net (code "125") (name "unconnected-(X1-PadA21)") (class "Default")
      (node (ref "X1") (pin "A21") (pinfunction "A21_A21") (pintype "passive"))
    )
    (net (code "126") (name "unconnected-(X1-PadA22)") (class "Default")
      (node (ref "X1") (pin "A22") (pinfunction "A22_A22") (pintype "passive"))
    )
    (net (code "127") (name "unconnected-(X1-PadA23)") (class "Default")
      (node (ref "X1") (pin "A23") (pinfunction "A23_A23") (pintype "passive"))
    )
    (net (code "128") (name "unconnected-(X1-PadA24)") (class "Default")
      (node (ref "X1") (pin "A24") (pinfunction "A24_A24") (pintype "passive"))
    )
    (net (code "129") (name "unconnected-(X1-PadA25)") (class "Default")
      (node (ref "X1") (pin "A25") (pinfunction "A25_A25") (pintype "passive"))
    )
    (net (code "130") (name "unconnected-(X1-PadA26)") (class "Default")
      (node (ref "X1") (pin "A26") (pinfunction "A26_A26") (pintype "passive"))
    )
    (net (code "131") (name "unconnected-(X1-PadA27)") (class "Default")
      (node (ref "X1") (pin "A27") (pinfunction "A27_A27") (pintype "passive"))
    )
    (net (code "132") (name "unconnected-(X1-PadA28)") (class "Default")
      (node (ref "X1") (pin "A28") (pinfunction "A28_A28") (pintype "passive"))
    )
    (net (code "133") (name "unconnected-(X1-PadA29)") (class "Default")
      (node (ref "X1") (pin "A29") (pinfunction "A29_A29") (pintype "passive"))
    )
    (net (code "134") (name "unconnected-(X1-PadA30)") (class "Default")
      (node (ref "X1") (pin "A30") (pinfunction "A30_A30") (pintype "passive"))
    )
    (net (code "135") (name "unconnected-(X1-PadC3)") (class "Default")
      (node (ref "X1") (pin "C3") (pinfunction "C3_C3") (pintype "passive"))
    )
    (net (code "136") (name "unconnected-(X1-PadC4)") (class "Default")
      (node (ref "X1") (pin "C4") (pinfunction "C4_C4") (pintype "passive"))
    )
    (net (code "137") (name "unconnected-(X1-PadC5)") (class "Default")
      (node (ref "X1") (pin "C5") (pinfunction "C5_C5") (pintype "passive"))
    )
    (net (code "138") (name "unconnected-(X1-PadC6)") (class "Default")
      (node (ref "X1") (pin "C6") (pinfunction "C6_C6") (pintype "passive"))
    )
    (net (code "139") (name "unconnected-(X1-PadC17)") (class "Default")
      (node (ref "X1") (pin "C17") (pinfunction "C17_C17") (pintype "passive"))
    )
    (net (code "140") (name "unconnected-(X1-PadC18)") (class "Default")
      (node (ref "X1") (pin "C18") (pinfunction "C18_C18") (pintype "passive"))
    )
    (net (code "141") (name "unconnected-(X1-PadC19)") (class "Default")
      (node (ref "X1") (pin "C19") (pinfunction "C19_C19") (pintype "passive"))
    )
    (net (code "142") (name "unconnected-(X1-PadC20)") (class "Default")
      (node (ref "X1") (pin "C20") (pinfunction "C20_C20") (pintype "passive"))
    )
    (net (code "143") (name "unconnected-(X1-PadC27)") (class "Default")
      (node (ref "X1") (pin "C27") (pinfunction "C27_C27") (pintype "passive"))
    )
    (net (code "144") (name "unconnected-(X1-PadC28)") (class "Default")
      (node (ref "X1") (pin "C28") (pinfunction "C28_C28") (pintype "passive"))
    )
    (net (code "145") (name "unconnected-(X1-PadC29)") (class "Default")
      (node (ref "X1") (pin "C29") (pinfunction "C29_C29") (pintype "passive"))
    )
    (net (code "146") (name "unconnected-(X1-PadC30)") (class "Default")
      (node (ref "X1") (pin "C30") (pinfunction "C30_C30") (pintype "passive"))
    )
    (net (code "147") (name "unconnected-(X2-PadA3)") (class "Default")
      (node (ref "X2") (pin "A3") (pinfunction "A3_A3") (pintype "passive"))
    )
    (net (code "148") (name "unconnected-(X2-PadA4)") (class "Default")
      (node (ref "X2") (pin "A4") (pinfunction "A4_A4") (pintype "passive"))
    )
    (net (code "149") (name "unconnected-(X2-PadA5)") (class "Default")
      (node (ref "X2") (pin "A5") (pinfunction "A5_A5") (pintype "passive"))
    )
    (net (code "150") (name "unconnected-(X2-PadA6)") (class "Default")
      (node (ref "X2") (pin "A6") (pinfunction "A6_A6") (pintype "passive"))
    )
    (net (code "151") (name "unconnected-(X2-PadA17)") (class "Default")
      (node (ref "X2") (pin "A17") (pinfunction "A17_A17") (pintype "passive"))
    )
    (net (code "152") (name "unconnected-(X2-PadA18)") (class "Default")
      (node (ref "X2") (pin "A18") (pinfunction "A18_A18") (pintype "passive"))
    )
    (net (code "153") (name "unconnected-(X2-PadA19)") (class "Default")
      (node (ref "X2") (pin "A19") (pinfunction "A19_A19") (pintype "passive"))
    )
    (net (code "154") (name "unconnected-(X2-PadA20)") (class "Default")
      (node (ref "X2") (pin "A20") (pinfunction "A20_A20") (pintype "passive"))
    )
    (net (code "155") (name "unconnected-(X2-PadA27)") (class "Default")
      (node (ref "X2") (pin "A27") (pinfunction "A27_A27") (pintype "passive"))
    )
    (net (code "156") (name "unconnected-(X2-PadA28)") (class "Default")
      (node (ref "X2") (pin "A28") (pinfunction "A28_A28") (pintype "passive"))
    )
    (net (code "157") (name "unconnected-(X2-PadA29)") (class "Default")
      (node (ref "X2") (pin "A29") (pinfunction "A29_A29") (pintype "passive"))
    )
    (net (code "158") (name "unconnected-(X2-PadA30)") (class "Default")
      (node (ref "X2") (pin "A30") (pinfunction "A30_A30") (pintype "passive"))
    )
    (net (code "159") (name "unconnected-(X2-PadC3)") (class "Default")
      (node (ref "X2") (pin "C3") (pinfunction "C3_C3") (pintype "passive"))
    )
    (net (code "160") (name "unconnected-(X2-PadC4)") (class "Default")
      (node (ref "X2") (pin "C4") (pinfunction "C4_C4") (pintype "passive"))
    )
    (net (code "161") (name "unconnected-(X2-PadC5)") (class "Default")
      (node (ref "X2") (pin "C5") (pinfunction "C5_C5") (pintype "passive"))
    )
    (net (code "162") (name "unconnected-(X2-PadC6)") (class "Default")
      (node (ref "X2") (pin "C6") (pinfunction "C6_C6") (pintype "passive"))
    )
    (net (code "163") (name "unconnected-(X2-PadC17)") (class "Default")
      (node (ref "X2") (pin "C17") (pinfunction "C17_C17") (pintype "passive"))
    )
    (net (code "164") (name "unconnected-(X2-PadC18)") (class "Default")
      (node (ref "X2") (pin "C18") (pinfunction "C18_C18") (pintype "passive"))
    )
    (net (code "165") (name "unconnected-(X2-PadC19)") (class "Default")
      (node (ref "X2") (pin "C19") (pinfunction "C19_C19") (pintype "passive"))
    )
    (net (code "166") (name "unconnected-(X2-PadC20)") (class "Default")
      (node (ref "X2") (pin "C20") (pinfunction "C20_C20") (pintype "passive"))
    )
    (net (code "167") (name "unconnected-(X2-PadC27)") (class "Default")
      (node (ref "X2") (pin "C27") (pinfunction "C27_C27") (pintype "passive"))
    )
    (net (code "168") (name "unconnected-(X2-PadC28)") (class "Default")
      (node (ref "X2") (pin "C28") (pinfunction "C28_C28") (pintype "passive"))
    )
    (net (code "169") (name "unconnected-(X2-PadC29)") (class "Default")
      (node (ref "X2") (pin "C29") (pinfunction "C29_C29") (pintype "passive"))
    )
    (net (code "170") (name "unconnected-(X2-PadC30)") (class "Default")
      (node (ref "X2") (pin "C30") (pinfunction "C30_C30") (pintype "passive"))
    )
    (net (code "171") (name "unconnected-(X3-PadA3)") (class "Default")
      (node (ref "X3") (pin "A3") (pinfunction "A3_A3") (pintype "passive"))
    )
    (net (code "172") (name "unconnected-(X3-PadA4)") (class "Default")
      (node (ref "X3") (pin "A4") (pinfunction "A4_A4") (pintype "passive"))
    )
    (net (code "173") (name "unconnected-(X3-PadA5)") (class "Default")
      (node (ref "X3") (pin "A5") (pinfunction "A5_A5") (pintype "passive"))
    )
    (net (code "174") (name "unconnected-(X3-PadA6)") (class "Default")
      (node (ref "X3") (pin "A6") (pinfunction "A6_A6") (pintype "passive"))
    )
    (net (code "175") (name "unconnected-(X3-PadA17)") (class "Default")
      (node (ref "X3") (pin "A17") (pinfunction "A17_A17") (pintype "passive"))
    )
    (net (code "176") (name "unconnected-(X3-PadA18)") (class "Default")
      (node (ref "X3") (pin "A18") (pinfunction "A18_A18") (pintype "passive"))
    )
    (net (code "177") (name "unconnected-(X3-PadA19)") (class "Default")
      (node (ref "X3") (pin "A19") (pinfunction "A19_A19") (pintype "passive"))
    )
    (net (code "178") (name "unconnected-(X3-PadA20)") (class "Default")
      (node (ref "X3") (pin "A20") (pinfunction "A20_A20") (pintype "passive"))
    )
    (net (code "179") (name "unconnected-(X3-PadA27)") (class "Default")
      (node (ref "X3") (pin "A27") (pinfunction "A27_A27") (pintype "passive"))
    )
    (net (code "180") (name "unconnected-(X3-PadA28)") (class "Default")
      (node (ref "X3") (pin "A28") (pinfunction "A28_A28") (pintype "passive"))
    )
    (net (code "181") (name "unconnected-(X3-PadA29)") (class "Default")
      (node (ref "X3") (pin "A29") (pinfunction "A29_A29") (pintype "passive"))
    )
    (net (code "182") (name "unconnected-(X3-PadA30)") (class "Default")
      (node (ref "X3") (pin "A30") (pinfunction "A30_A30") (pintype "passive"))
    )
    (net (code "183") (name "unconnected-(X3-PadC3)") (class "Default")
      (node (ref "X3") (pin "C3") (pinfunction "C3_C3") (pintype "passive"))
    )
    (net (code "184") (name "unconnected-(X3-PadC4)") (class "Default")
      (node (ref "X3") (pin "C4") (pinfunction "C4_C4") (pintype "passive"))
    )
    (net (code "185") (name "unconnected-(X3-PadC5)") (class "Default")
      (node (ref "X3") (pin "C5") (pinfunction "C5_C5") (pintype "passive"))
    )
    (net (code "186") (name "unconnected-(X3-PadC6)") (class "Default")
      (node (ref "X3") (pin "C6") (pinfunction "C6_C6") (pintype "passive"))
    )
    (net (code "187") (name "unconnected-(X3-PadC17)") (class "Default")
      (node (ref "X3") (pin "C17") (pinfunction "C17_C17") (pintype "passive"))
    )
    (net (code "188") (name "unconnected-(X3-PadC18)") (class "Default")
      (node (ref "X3") (pin "C18") (pinfunction "C18_C18") (pintype "passive"))
    )
    (net (code "189") (name "unconnected-(X3-PadC19)") (class "Default")
      (node (ref "X3") (pin "C19") (pinfunction "C19_C19") (pintype "passive"))
    )
    (net (code "190") (name "unconnected-(X3-PadC20)") (class "Default")
      (node (ref "X3") (pin "C20") (pinfunction "C20_C20") (pintype "passive"))
    )
    (net (code "191") (name "unconnected-(X3-PadC27)") (class "Default")
      (node (ref "X3") (pin "C27") (pinfunction "C27_C27") (pintype "passive"))
    )
    (net (code "192") (name "unconnected-(X3-PadC28)") (class "Default")
      (node (ref "X3") (pin "C28") (pinfunction "C28_C28") (pintype "passive"))
    )
    (net (code "193") (name "unconnected-(X3-PadC29)") (class "Default")
      (node (ref "X3") (pin "C29") (pinfunction "C29_C29") (pintype "passive"))
    )
    (net (code "194") (name "unconnected-(X3-PadC30)") (class "Default")
      (node (ref "X3") (pin "C30") (pinfunction "C30_C30") (pintype "passive"))
    )
    (net (code "195") (name "unconnected-(X4-PadA3)") (class "Default")
      (node (ref "X4") (pin "A3") (pinfunction "A3_A3") (pintype "passive"))
    )
    (net (code "196") (name "unconnected-(X4-PadA4)") (class "Default")
      (node (ref "X4") (pin "A4") (pinfunction "A4_A4") (pintype "passive"))
    )
    (net (code "197") (name "unconnected-(X4-PadA5)") (class "Default")
      (node (ref "X4") (pin "A5") (pinfunction "A5_A5") (pintype "passive"))
    )
    (net (code "198") (name "unconnected-(X4-PadA6)") (class "Default")
      (node (ref "X4") (pin "A6") (pinfunction "A6_A6") (pintype "passive"))
    )
    (net (code "199") (name "unconnected-(X4-PadA17)") (class "Default")
      (node (ref "X4") (pin "A17") (pinfunction "A17_A17") (pintype "passive"))
    )
    (net (code "200") (name "unconnected-(X4-PadA18)") (class "Default")
      (node (ref "X4") (pin "A18") (pinfunction "A18_A18") (pintype "passive"))
    )
    (net (code "201") (name "unconnected-(X4-PadA19)") (class "Default")
      (node (ref "X4") (pin "A19") (pinfunction "A19_A19") (pintype "passive"))
    )
    (net (code "202") (name "unconnected-(X4-PadA20)") (class "Default")
      (node (ref "X4") (pin "A20") (pinfunction "A20_A20") (pintype "passive"))
    )
    (net (code "203") (name "unconnected-(X4-PadA27)") (class "Default")
      (node (ref "X4") (pin "A27") (pinfunction "A27_A27") (pintype "passive"))
    )
    (net (code "204") (name "unconnected-(X4-PadA28)") (class "Default")
      (node (ref "X4") (pin "A28") (pinfunction "A28_A28") (pintype "passive"))
    )
    (net (code "205") (name "unconnected-(X4-PadA29)") (class "Default")
      (node (ref "X4") (pin "A29") (pinfunction "A29_A29") (pintype "passive"))
    )
    (net (code "206") (name "unconnected-(X4-PadA30)") (class "Default")
      (node (ref "X4") (pin "A30") (pinfunction "A30_A30") (pintype "passive"))
    )
    (net (code "207") (name "unconnected-(X4-PadC3)") (class "Default")
      (node (ref "X4") (pin "C3") (pinfunction "C3_C3") (pintype "passive"))
    )
    (net (code "208") (name "unconnected-(X4-PadC4)") (class "Default")
      (node (ref "X4") (pin "C4") (pinfunction "C4_C4") (pintype "passive"))
    )
    (net (code "209") (name "unconnected-(X4-PadC5)") (class "Default")
      (node (ref "X4") (pin "C5") (pinfunction "C5_C5") (pintype "passive"))
    )
    (net (code "210") (name "unconnected-(X4-PadC6)") (class "Default")
      (node (ref "X4") (pin "C6") (pinfunction "C6_C6") (pintype "passive"))
    )
    (net (code "211") (name "unconnected-(X4-PadC17)") (class "Default")
      (node (ref "X4") (pin "C17") (pinfunction "C17_C17") (pintype "passive"))
    )
    (net (code "212") (name "unconnected-(X4-PadC18)") (class "Default")
      (node (ref "X4") (pin "C18") (pinfunction "C18_C18") (pintype "passive"))
    )
    (net (code "213") (name "unconnected-(X4-PadC19)") (class "Default")
      (node (ref "X4") (pin "C19") (pinfunction "C19_C19") (pintype "passive"))
    )
    (net (code "214") (name "unconnected-(X4-PadC20)") (class "Default")
      (node (ref "X4") (pin "C20") (pinfunction "C20_C20") (pintype "passive"))
    )
    (net (code "215") (name "unconnected-(X4-PadC27)") (class "Default")
      (node (ref "X4") (pin "C27") (pinfunction "C27_C27") (pintype "passive"))
    )
    (net (code "216") (name "unconnected-(X4-PadC28)") (class "Default")
      (node (ref "X4") (pin "C28") (pinfunction "C28_C28") (pintype "passive"))
    )
    (net (code "217") (name "unconnected-(X4-PadC29)") (class "Default")
      (node (ref "X4") (pin "C29") (pinfunction "C29_C29") (pintype "passive"))
    )
    (net (code "218") (name "unconnected-(X4-PadC30)") (class "Default")
      (node (ref "X4") (pin "C30") (pinfunction "C30_C30") (pintype "passive"))
    )
    (net (code "219") (name "unconnected-(X5-PadA3)") (class "Default")
      (node (ref "X5") (pin "A3") (pinfunction "A3_A3") (pintype "passive"))
    )
    (net (code "220") (name "unconnected-(X5-PadA4)") (class "Default")
      (node (ref "X5") (pin "A4") (pinfunction "A4_A4") (pintype "passive"))
    )
    (net (code "221") (name "unconnected-(X5-PadA5)") (class "Default")
      (node (ref "X5") (pin "A5") (pinfunction "A5_A5") (pintype "passive"))
    )
    (net (code "222") (name "unconnected-(X5-PadA6)") (class "Default")
      (node (ref "X5") (pin "A6") (pinfunction "A6_A6") (pintype "passive"))
    )
    (net (code "223") (name "unconnected-(X5-PadA17)") (class "Default")
      (node (ref "X5") (pin "A17") (pinfunction "A17_A17") (pintype "passive"))
    )
    (net (code "224") (name "unconnected-(X5-PadA18)") (class "Default")
      (node (ref "X5") (pin "A18") (pinfunction "A18_A18") (pintype "passive"))
    )
    (net (code "225") (name "unconnected-(X5-PadA19)") (class "Default")
      (node (ref "X5") (pin "A19") (pinfunction "A19_A19") (pintype "passive"))
    )
    (net (code "226") (name "unconnected-(X5-PadA20)") (class "Default")
      (node (ref "X5") (pin "A20") (pinfunction "A20_A20") (pintype "passive"))
    )
    (net (code "227") (name "unconnected-(X5-PadA27)") (class "Default")
      (node (ref "X5") (pin "A27") (pinfunction "A27_A27") (pintype "passive"))
    )
    (net (code "228") (name "unconnected-(X5-PadA28)") (class "Default")
      (node (ref "X5") (pin "A28") (pinfunction "A28_A28") (pintype "passive"))
    )
    (net (code "229") (name "unconnected-(X5-PadA29)") (class "Default")
      (node (ref "X5") (pin "A29") (pinfunction "A29_A29") (pintype "passive"))
    )
    (net (code "230") (name "unconnected-(X5-PadA30)") (class "Default")
      (node (ref "X5") (pin "A30") (pinfunction "A30_A30") (pintype "passive"))
    )
    (net (code "231") (name "unconnected-(X5-PadC3)") (class "Default")
      (node (ref "X5") (pin "C3") (pinfunction "C3_C3") (pintype "passive"))
    )
    (net (code "232") (name "unconnected-(X5-PadC4)") (class "Default")
      (node (ref "X5") (pin "C4") (pinfunction "C4_C4") (pintype "passive"))
    )
    (net (code "233") (name "unconnected-(X5-PadC5)") (class "Default")
      (node (ref "X5") (pin "C5") (pinfunction "C5_C5") (pintype "passive"))
    )
    (net (code "234") (name "unconnected-(X5-PadC6)") (class "Default")
      (node (ref "X5") (pin "C6") (pinfunction "C6_C6") (pintype "passive"))
    )
    (net (code "235") (name "unconnected-(X5-PadC17)") (class "Default")
      (node (ref "X5") (pin "C17") (pinfunction "C17_C17") (pintype "passive"))
    )
    (net (code "236") (name "unconnected-(X5-PadC18)") (class "Default")
      (node (ref "X5") (pin "C18") (pinfunction "C18_C18") (pintype "passive"))
    )
    (net (code "237") (name "unconnected-(X5-PadC19)") (class "Default")
      (node (ref "X5") (pin "C19") (pinfunction "C19_C19") (pintype "passive"))
    )
    (net (code "238") (name "unconnected-(X5-PadC20)") (class "Default")
      (node (ref "X5") (pin "C20") (pinfunction "C20_C20") (pintype "passive"))
    )
    (net (code "239") (name "unconnected-(X5-PadC27)") (class "Default")
      (node (ref "X5") (pin "C27") (pinfunction "C27_C27") (pintype "passive"))
    )
    (net (code "240") (name "unconnected-(X5-PadC28)") (class "Default")
      (node (ref "X5") (pin "C28") (pinfunction "C28_C28") (pintype "passive"))
    )
    (net (code "241") (name "unconnected-(X5-PadC29)") (class "Default")
      (node (ref "X5") (pin "C29") (pinfunction "C29_C29") (pintype "passive"))
    )
    (net (code "242") (name "unconnected-(X5-PadC30)") (class "Default")
      (node (ref "X5") (pin "C30") (pinfunction "C30_C30") (pintype "passive"))
    )
    (net (code "243") (name "unconnected-(X6-PadA3)") (class "Default")
      (node (ref "X6") (pin "A3") (pinfunction "A3_A3") (pintype "passive"))
    )
    (net (code "244") (name "unconnected-(X6-PadA4)") (class "Default")
      (node (ref "X6") (pin "A4") (pinfunction "A4_A4") (pintype "passive"))
    )
    (net (code "245") (name "unconnected-(X6-PadA5)") (class "Default")
      (node (ref "X6") (pin "A5") (pinfunction "A5_A5") (pintype "passive"))
    )
    (net (code "246") (name "unconnected-(X6-PadA6)") (class "Default")
      (node (ref "X6") (pin "A6") (pinfunction "A6_A6") (pintype "passive"))
    )
    (net (code "247") (name "unconnected-(X6-PadA17)") (class "Default")
      (node (ref "X6") (pin "A17") (pinfunction "A17_A17") (pintype "passive"))
    )
    (net (code "248") (name "unconnected-(X6-PadA18)") (class "Default")
      (node (ref "X6") (pin "A18") (pinfunction "A18_A18") (pintype "passive"))
    )
    (net (code "249") (name "unconnected-(X6-PadA19)") (class "Default")
      (node (ref "X6") (pin "A19") (pinfunction "A19_A19") (pintype "passive"))
    )
    (net (code "250") (name "unconnected-(X6-PadA20)") (class "Default")
      (node (ref "X6") (pin "A20") (pinfunction "A20_A20") (pintype "passive"))
    )
    (net (code "251") (name "unconnected-(X6-PadA27)") (class "Default")
      (node (ref "X6") (pin "A27") (pinfunction "A27_A27") (pintype "passive"))
    )
    (net (code "252") (name "unconnected-(X6-PadA28)") (class "Default")
      (node (ref "X6") (pin "A28") (pinfunction "A28_A28") (pintype "passive"))
    )
    (net (code "253") (name "unconnected-(X6-PadA29)") (class "Default")
      (node (ref "X6") (pin "A29") (pinfunction "A29_A29") (pintype "passive"))
    )
    (net (code "254") (name "unconnected-(X6-PadA30)") (class "Default")
      (node (ref "X6") (pin "A30") (pinfunction "A30_A30") (pintype "passive"))
    )
    (net (code "255") (name "unconnected-(X6-PadC3)") (class "Default")
      (node (ref "X6") (pin "C3") (pinfunction "C3_C3") (pintype "passive"))
    )
    (net (code "256") (name "unconnected-(X6-PadC4)") (class "Default")
      (node (ref "X6") (pin "C4") (pinfunction "C4_C4") (pintype "passive"))
    )
    (net (code "257") (name "unconnected-(X6-PadC5)") (class "Default")
      (node (ref "X6") (pin "C5") (pinfunction "C5_C5") (pintype "passive"))
    )
    (net (code "258") (name "unconnected-(X6-PadC6)") (class "Default")
      (node (ref "X6") (pin "C6") (pinfunction "C6_C6") (pintype "passive"))
    )
    (net (code "259") (name "unconnected-(X6-PadC17)") (class "Default")
      (node (ref "X6") (pin "C17") (pinfunction "C17_C17") (pintype "passive"))
    )
    (net (code "260") (name "unconnected-(X6-PadC18)") (class "Default")
      (node (ref "X6") (pin "C18") (pinfunction "C18_C18") (pintype "passive"))
    )
    (net (code "261") (name "unconnected-(X6-PadC19)") (class "Default")
      (node (ref "X6") (pin "C19") (pinfunction "C19_C19") (pintype "passive"))
    )
    (net (code "262") (name "unconnected-(X6-PadC20)") (class "Default")
      (node (ref "X6") (pin "C20") (pinfunction "C20_C20") (pintype "passive"))
    )
    (net (code "263") (name "unconnected-(X6-PadC27)") (class "Default")
      (node (ref "X6") (pin "C27") (pinfunction "C27_C27") (pintype "passive"))
    )
    (net (code "264") (name "unconnected-(X6-PadC28)") (class "Default")
      (node (ref "X6") (pin "C28") (pinfunction "C28_C28") (pintype "passive"))
    )
    (net (code "265") (name "unconnected-(X6-PadC29)") (class "Default")
      (node (ref "X6") (pin "C29") (pinfunction "C29_C29") (pintype "passive"))
    )
    (net (code "266") (name "unconnected-(X6-PadC30)") (class "Default")
      (node (ref "X6") (pin "C30") (pinfunction "C30_C30") (pintype "passive"))
    )
    (net (code "267") (name "unconnected-(X7-PadA3)") (class "Default")
      (node (ref "X7") (pin "A3") (pinfunction "A3_A3") (pintype "passive"))
    )
    (net (code "268") (name "unconnected-(X7-PadA4)") (class "Default")
      (node (ref "X7") (pin "A4") (pinfunction "A4_A4") (pintype "passive"))
    )
    (net (code "269") (name "unconnected-(X7-PadA5)") (class "Default")
      (node (ref "X7") (pin "A5") (pinfunction "A5_A5") (pintype "passive"))
    )
    (net (code "270") (name "unconnected-(X7-PadA6)") (class "Default")
      (node (ref "X7") (pin "A6") (pinfunction "A6_A6") (pintype "passive"))
    )
    (net (code "271") (name "unconnected-(X7-PadA17)") (class "Default")
      (node (ref "X7") (pin "A17") (pinfunction "A17_A17") (pintype "passive"))
    )
    (net (code "272") (name "unconnected-(X7-PadA18)") (class "Default")
      (node (ref "X7") (pin "A18") (pinfunction "A18_A18") (pintype "passive"))
    )
    (net (code "273") (name "unconnected-(X7-PadA19)") (class "Default")
      (node (ref "X7") (pin "A19") (pinfunction "A19_A19") (pintype "passive"))
    )
    (net (code "274") (name "unconnected-(X7-PadA20)") (class "Default")
      (node (ref "X7") (pin "A20") (pinfunction "A20_A20") (pintype "passive"))
    )
    (net (code "275") (name "unconnected-(X7-PadA27)") (class "Default")
      (node (ref "X7") (pin "A27") (pinfunction "A27_A27") (pintype "passive"))
    )
    (net (code "276") (name "unconnected-(X7-PadA28)") (class "Default")
      (node (ref "X7") (pin "A28") (pinfunction "A28_A28") (pintype "passive"))
    )
    (net (code "277") (name "unconnected-(X7-PadA29)") (class "Default")
      (node (ref "X7") (pin "A29") (pinfunction "A29_A29") (pintype "passive"))
    )
    (net (code "278") (name "unconnected-(X7-PadA30)") (class "Default")
      (node (ref "X7") (pin "A30") (pinfunction "A30_A30") (pintype "passive"))
    )
    (net (code "279") (name "unconnected-(X7-PadC3)") (class "Default")
      (node (ref "X7") (pin "C3") (pinfunction "C3_C3") (pintype "passive"))
    )
    (net (code "280") (name "unconnected-(X7-PadC4)") (class "Default")
      (node (ref "X7") (pin "C4") (pinfunction "C4_C4") (pintype "passive"))
    )
    (net (code "281") (name "unconnected-(X7-PadC5)") (class "Default")
      (node (ref "X7") (pin "C5") (pinfunction "C5_C5") (pintype "passive"))
    )
    (net (code "282") (name "unconnected-(X7-PadC6)") (class "Default")
      (node (ref "X7") (pin "C6") (pinfunction "C6_C6") (pintype "passive"))
    )
    (net (code "283") (name "unconnected-(X7-PadC17)") (class "Default")
      (node (ref "X7") (pin "C17") (pinfunction "C17_C17") (pintype "passive"))
    )
    (net (code "284") (name "unconnected-(X7-PadC18)") (class "Default")
      (node (ref "X7") (pin "C18") (pinfunction "C18_C18") (pintype "passive"))
    )
    (net (code "285") (name "unconnected-(X7-PadC19)") (class "Default")
      (node (ref "X7") (pin "C19") (pinfunction "C19_C19") (pintype "passive"))
    )
    (net (code "286") (name "unconnected-(X7-PadC20)") (class "Default")
      (node (ref "X7") (pin "C20") (pinfunction "C20_C20") (pintype "passive"))
    )
    (net (code "287") (name "unconnected-(X7-PadC27)") (class "Default")
      (node (ref "X7") (pin "C27") (pinfunction "C27_C27") (pintype "passive"))
    )
    (net (code "288") (name "unconnected-(X7-PadC28)") (class "Default")
      (node (ref "X7") (pin "C28") (pinfunction "C28_C28") (pintype "passive"))
    )
    (net (code "289") (name "unconnected-(X7-PadC29)") (class "Default")
      (node (ref "X7") (pin "C29") (pinfunction "C29_C29") (pintype "passive"))
    )
    (net (code "290") (name "unconnected-(X7-PadC30)") (class "Default")
      (node (ref "X7") (pin "C30") (pinfunction "C30_C30") (pintype "passive"))
    )
  )
)
